# IR.net
KiCad netlist of a schematic drawn in Altium Designer
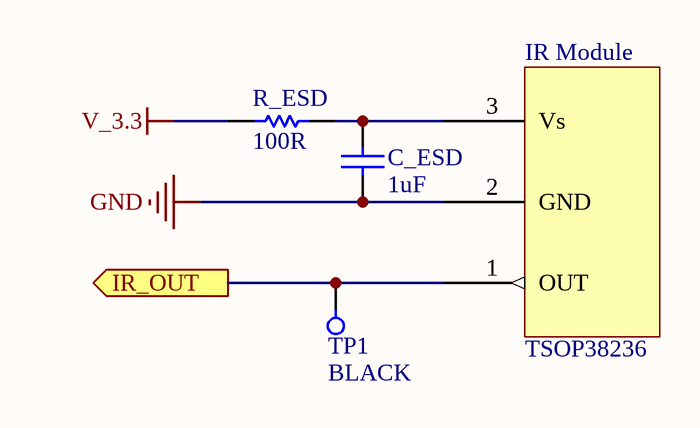
[diagram p0: IR.SchDoc]

(export (version "E")
  (design (tool "Eeschema 10.0.6"))
  (components
    (comp (ref "C_ESD")
      (value "1uF")
      (footprint "0603")
      (description "CAP CER 1.0UF 50V X7R 0603")
      (fields (field (name "MANUFACTURER") "Taiyo Yuden"))
      (libsource (lib "ENEL429_1") (part "CP_1uF_50V_0603"))
    )
    (comp (ref "IR Module")
      (value "TSOP38236")
      (footprint "TSOP38236 IR Receiver")
      (libsource (lib "Wacky_1") (part "TSOP38236"))
    )
    (comp (ref "R_ESD")
      (value "100R")
      (footprint "0603")
      (description "RES 100 OHM 1/10W 1% 0603 SMD")
      (fields (field (name "MANUFACTURER") "ROHM"))
      (libsource (lib "ENEL429_1") (part "RS_100R 0603"))
    )
    (comp (ref "TP1")
      (value "BLACK")
      (footprint "testpoint-small")
      (description "TEST POINT PC MINI .040\"D BLACK")
      (fields (field (name "PART NUMBER") "TP5001"))
      (libsource (lib "ECE_Component_Library_2") (part "TP5001"))
    )
  )
  (nets
    (net (code "1") (name "/IR_OUT") (class "Default")
      (node (ref "IR Module") (pin "1") (pinfunction "OUT_1") (pintype "output"))
      (node (ref "TP1") (pin "1") (pinfunction "1_1") (pintype "passive"))
    )
    (net (code "2") (name "GND") (class "Default")
      (node (ref "C_ESD") (pin "1") (pinfunction "1_1") (pintype "passive"))
      (node (ref "IR Module") (pin "2") (pinfunction "GND_2") (pintype "power_in"))
    )
    (net (code "3") (name "Net-(IR Module-Vs)") (class "Default")
      (node (ref "C_ESD") (pin "2") (pinfunction "2_2") (pintype "passive"))
      (node (ref "IR Module") (pin "3") (pinfunction "Vs_3") (pintype "power_in"))
      (node (ref "R_ESD") (pin "2") (pinfunction "2_2") (pintype "passive"))
    )
    (net (code "4") (name "V_3.3") (class "Default")
      (node (ref "R_ESD") (pin "1") (pinfunction "1_1") (pintype "passive"))
    )
  )
)
